# design_god.net
KiCad netlist of a schematic drawn in EAGLE
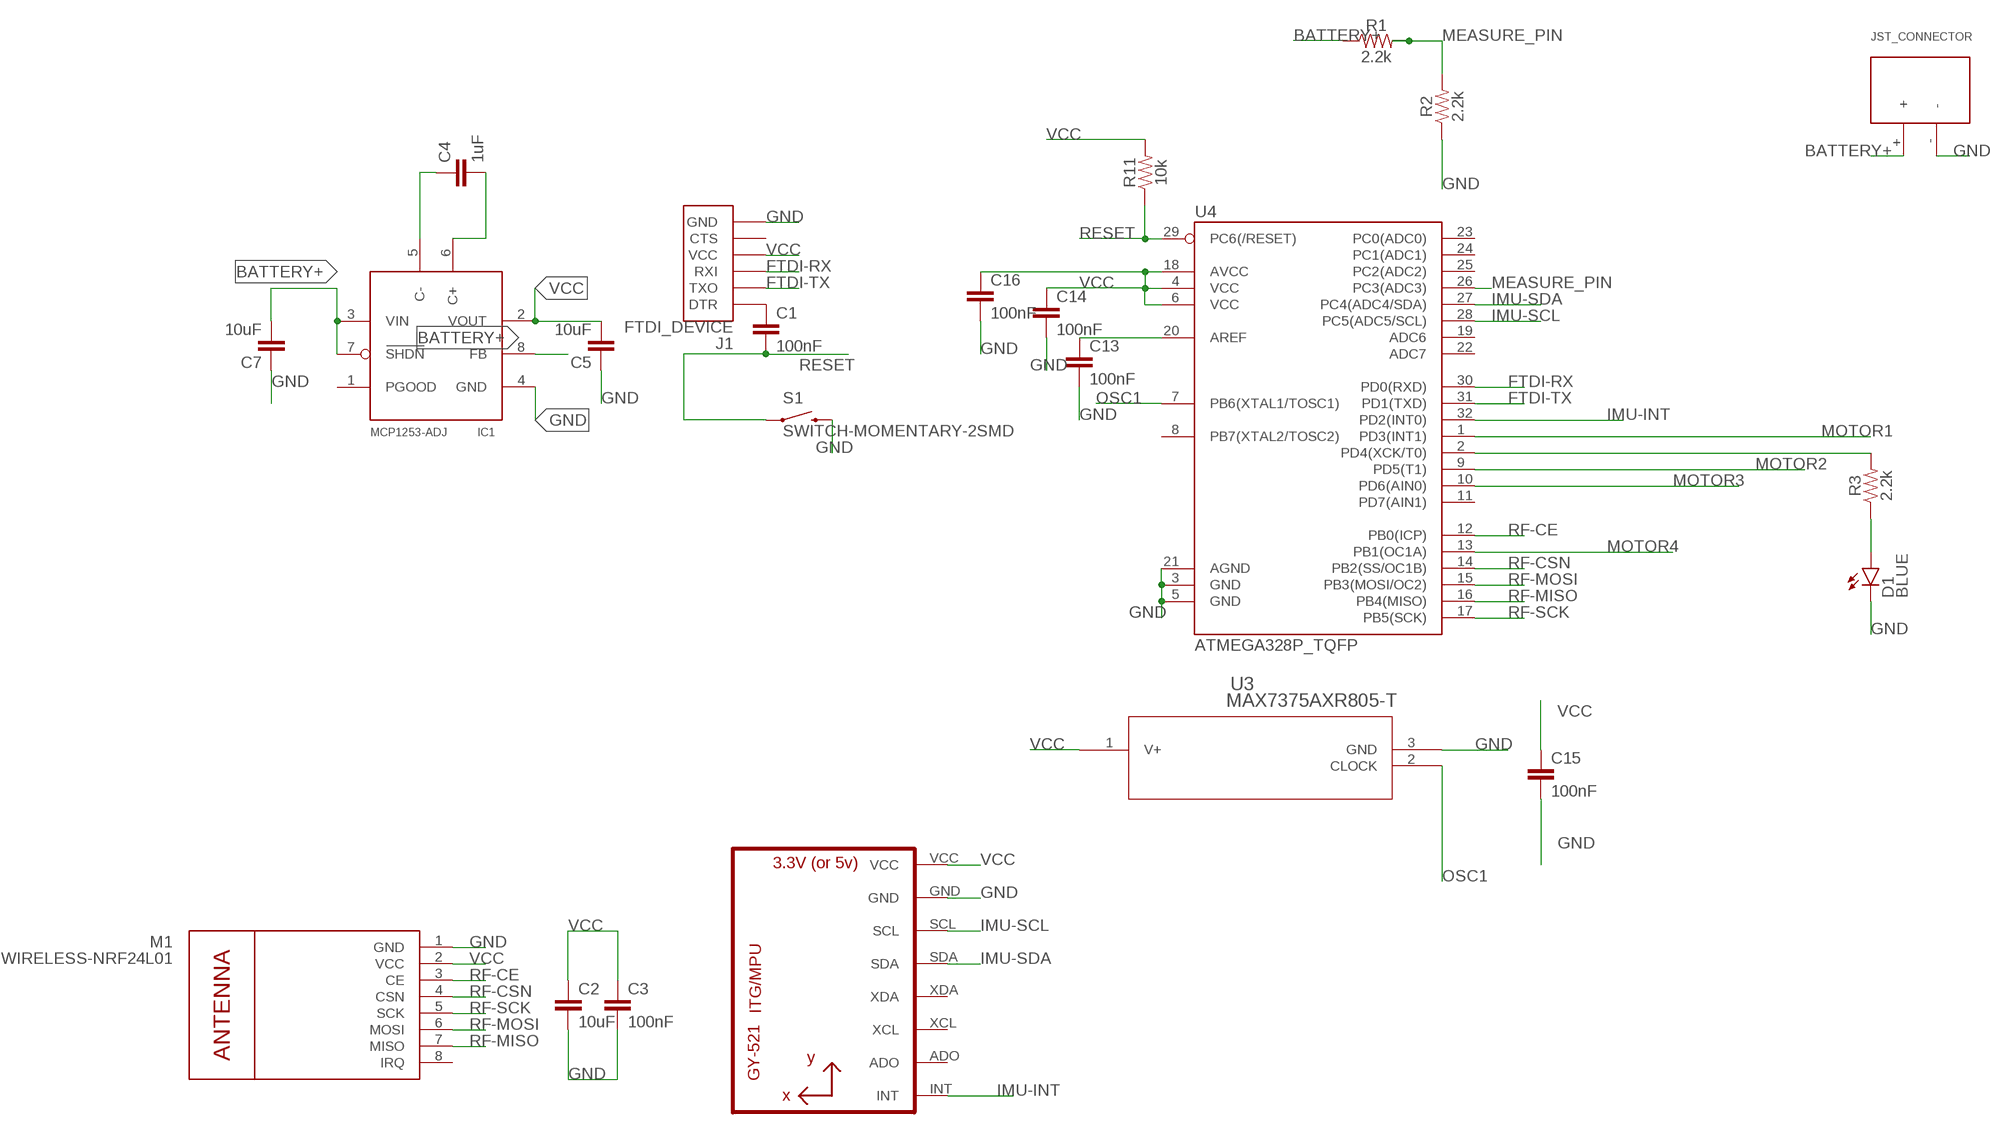
[diagram p0: schematic, sheet 1, part 1 of 2]
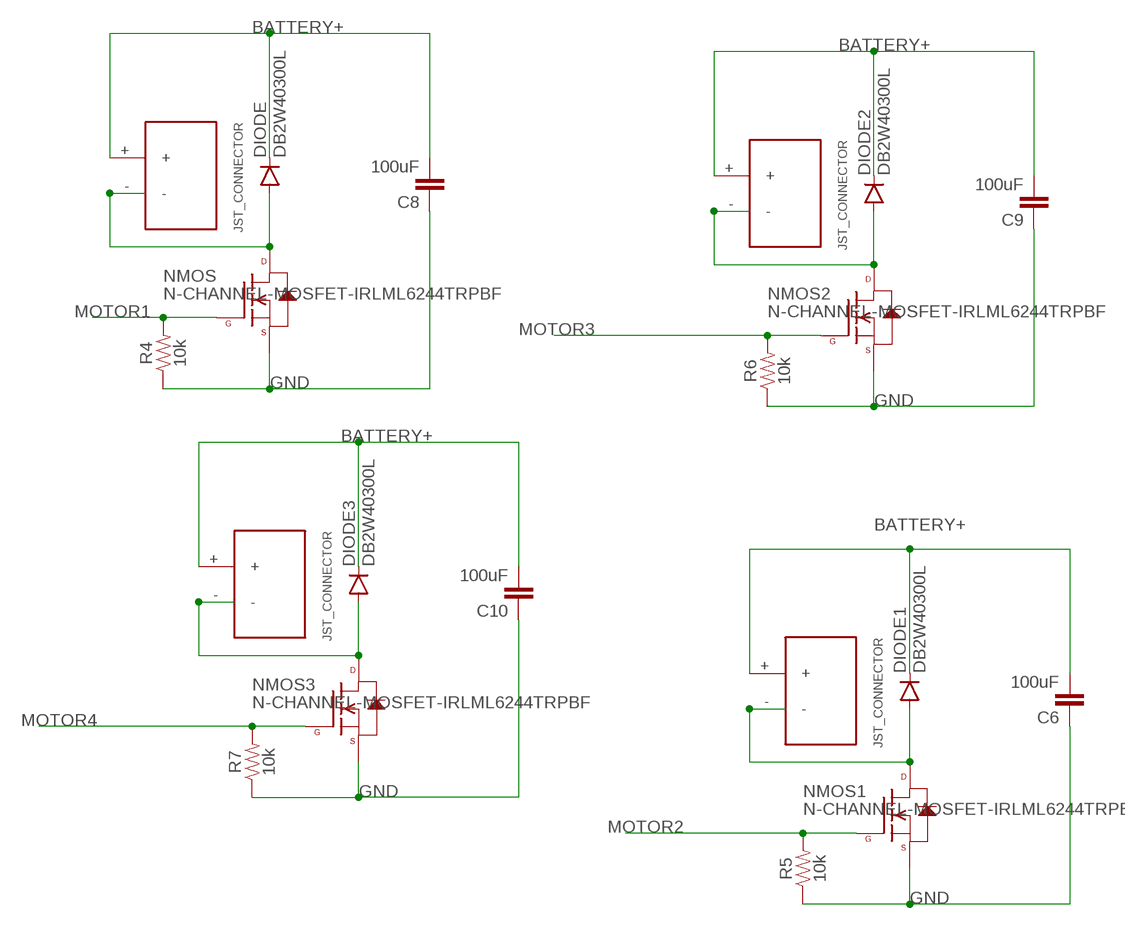
[diagram p1: schematic, sheet 1, part 2 of 2]

(export (version "E")
  (design (tool "Eeschema 10.0.6"))
  (components
    (comp (ref "C1")
      (value "100nF")
      (footprint "eagle-import:0603-CAP")
      (libsource (lib "eagle-import") (part "0.1UF-25V(+80/-20%)(0603)"))
    )
    (comp (ref "C2")
      (value "10uF")
      (footprint "eagle-import:0603-CAP")
      (libsource (lib "eagle-import") (part "CAP0603-CAP"))
    )
    (comp (ref "C3")
      (value "100nF")
      (footprint "eagle-import:0603-CAP")
      (libsource (lib "eagle-import") (part "CAP0603-CAP"))
    )
    (comp (ref "C4")
      (value "1uF")
      (footprint "eagle-import:0603-CAP")
      (libsource (lib "eagle-import") (part "0.1UF-25V(+80/-20%)(0603)"))
    )
    (comp (ref "C5")
      (value "10uF")
      (footprint "eagle-import:0603-CAP")
      (libsource (lib "eagle-import") (part "0.1UF-25V(+80/-20%)(0603)"))
    )
    (comp (ref "C6")
      (value "100uF")
      (footprint "eagle-import:1206")
      (libsource (lib "eagle-import") (part "CAP1206"))
    )
    (comp (ref "C7")
      (value "10uF")
      (footprint "eagle-import:0603-CAP")
      (libsource (lib "eagle-import") (part "0.1UF-25V(+80/-20%)(0603)"))
    )
    (comp (ref "C8")
      (value "100uF")
      (footprint "eagle-import:1206")
      (libsource (lib "eagle-import") (part "CAP1206"))
    )
    (comp (ref "C9")
      (value "100uF")
      (footprint "eagle-import:1206")
      (libsource (lib "eagle-import") (part "CAP1206"))
    )
    (comp (ref "C10")
      (value "100uF")
      (footprint "eagle-import:1206")
      (libsource (lib "eagle-import") (part "CAP1206"))
    )
    (comp (ref "C13")
      (value "100nF")
      (footprint "eagle-import:0603-CAP")
      (libsource (lib "eagle-import") (part "CAP0603-CAP"))
    )
    (comp (ref "C14")
      (value "100nF")
      (footprint "eagle-import:0603-CAP")
      (libsource (lib "eagle-import") (part "CAP0603-CAP"))
    )
    (comp (ref "C15")
      (value "100nF")
      (footprint "eagle-import:0603-CAP")
      (libsource (lib "eagle-import") (part "0.1UF-25V(+80/-20%)(0603)"))
    )
    (comp (ref "C16")
      (value "100nF")
      (footprint "eagle-import:0603-CAP")
      (libsource (lib "eagle-import") (part "CAP0603-CAP"))
    )
    (comp (ref "D1")
      (value "BLUE")
      (footprint "eagle-import:LED-0603")
      (fields (field (name "SPICEPREFIX") "D"))
      (libsource (lib "eagle-import") (part "LED-BLUE0603"))
    )
    (comp (ref "DIODE")
      (value "DB2W40300L")
      (footprint "eagle-import:MINI2-F3-B")
      (libsource (lib "eagle-import") (part "DB2W40300L"))
    )
    (comp (ref "DIODE1")
      (value "DB2W40300L")
      (footprint "eagle-import:MINI2-F3-B")
      (libsource (lib "eagle-import") (part "DB2W40300L"))
    )
    (comp (ref "DIODE2")
      (value "DB2W40300L")
      (footprint "eagle-import:MINI2-F3-B")
      (libsource (lib "eagle-import") (part "DB2W40300L"))
    )
    (comp (ref "DIODE3")
      (value "DB2W40300L")
      (footprint "eagle-import:MINI2-F3-B")
      (libsource (lib "eagle-import") (part "DB2W40300L"))
    )
    (comp (ref "IC1")
      (value "MCP1253-ADJ")
      (footprint "eagle-import:MSOP8")
      (libsource (lib "eagle-import") (part "MCP1253-ADJ"))
    )
    (comp (ref "J1")
      (value "FTDI_DEVICE")
      (footprint "eagle-import:FTDI_DEVICE_SIDE")
      (libsource (lib "eagle-import") (part "FTDI_DEVICE"))
    )
    (comp (ref "M1")
      (value "WIRELESS-NRF24L01")
      (footprint "eagle-import:WIRELESS-NRF24L01")
      (libsource (lib "eagle-import") (part "WIRELESS-NRF24L01"))
    )
    (comp (ref "MOTOR1")
      (value "JST_CONNECTOR_FEMALE")
      (footprint "eagle-import:JST_CONNECTOR_FEMALE")
      (libsource (lib "eagle-import") (part "JST_CONNECTOR_FEMALE"))
    )
    (comp (ref "MOTOR2")
      (value "JST_CONNECTOR_FEMALE")
      (footprint "eagle-import:JST_CONNECTOR_FEMALE")
      (libsource (lib "eagle-import") (part "JST_CONNECTOR_FEMALE"))
    )
    (comp (ref "MOTOR3")
      (value "JST_CONNECTOR_FEMALE")
      (footprint "eagle-import:JST_CONNECTOR_FEMALE")
      (libsource (lib "eagle-import") (part "JST_CONNECTOR_FEMALE"))
    )
    (comp (ref "MOTOR4")
      (value "JST_CONNECTOR_FEMALE")
      (footprint "eagle-import:JST_CONNECTOR_FEMALE")
      (libsource (lib "eagle-import") (part "JST_CONNECTOR_FEMALE"))
    )
    (comp (ref "NMOS")
      (value "N-CHANNEL-MOSFET-IRLML6244TRPBF")
      (footprint "eagle-import:SOT23-3")
      (libsource (lib "eagle-import") (part "N-CHANNEL-MOSFET-IRLML6244TRPBF"))
    )
    (comp (ref "NMOS1")
      (value "N-CHANNEL-MOSFET-IRLML6244TRPBF")
      (footprint "eagle-import:SOT23-3")
      (libsource (lib "eagle-import") (part "N-CHANNEL-MOSFET-IRLML6244TRPBF"))
    )
    (comp (ref "NMOS2")
      (value "N-CHANNEL-MOSFET-IRLML6244TRPBF")
      (footprint "eagle-import:SOT23-3")
      (libsource (lib "eagle-import") (part "N-CHANNEL-MOSFET-IRLML6244TRPBF"))
    )
    (comp (ref "NMOS3")
      (value "N-CHANNEL-MOSFET-IRLML6244TRPBF")
      (footprint "eagle-import:SOT23-3")
      (libsource (lib "eagle-import") (part "N-CHANNEL-MOSFET-IRLML6244TRPBF"))
    )
    (comp (ref "R1")
      (value "2.2k")
      (footprint "eagle-import:0603")
      (libsource (lib "eagle-import") (part "2.2KOHM-0603-1/10W-1%"))
    )
    (comp (ref "R2")
      (value "2.2k")
      (footprint "eagle-import:0603")
      (libsource (lib "eagle-import") (part "2.2KOHM-0603-1/10W-1%"))
    )
    (comp (ref "R3")
      (value "2.2k")
      (footprint "eagle-import:0603")
      (fields (field (name "SPICEPREFIX") "R"))
      (libsource (lib "eagle-import") (part "2.2KOHM-0603-1/10W-1%"))
    )
    (comp (ref "R4")
      (value "10k")
      (footprint "eagle-import:0603")
      (libsource (lib "eagle-import") (part "2.2KOHM-0603-1/10W-1%"))
    )
    (comp (ref "R5")
      (value "10k")
      (footprint "eagle-import:0603")
      (libsource (lib "eagle-import") (part "2.2KOHM-0603-1/10W-1%"))
    )
    (comp (ref "R6")
      (value "10k")
      (footprint "eagle-import:0603")
      (libsource (lib "eagle-import") (part "2.2KOHM-0603-1/10W-1%"))
    )
    (comp (ref "R7")
      (value "10k")
      (footprint "eagle-import:0603")
      (libsource (lib "eagle-import") (part "2.2KOHM-0603-1/10W-1%"))
    )
    (comp (ref "R11")
      (value "10k")
      (footprint "eagle-import:0603")
      (libsource (lib "eagle-import") (part "2.2KOHM-0603-1/10W-1%"))
    )
    (comp (ref "S1")
      (value "SWITCH-MOMENTARY-2SMD")
      (footprint "eagle-import:TACTILE-SWITCH-SMD")
      (libsource (lib "eagle-import") (part "SWITCH-MOMENTARY-2SMD"))
    )
    (comp (ref "U$1")
      (value "JST_CONNECTOR_FEMALE")
      (footprint "eagle-import:JST_CONNECTOR_FEMALE")
      (libsource (lib "eagle-import") (part "JST_CONNECTOR_FEMALE"))
    )
    (comp (ref "U2")
      (value "GY-521MPU6050")
      (footprint "eagle-import:GY-521")
      (libsource (lib "eagle-import") (part "GY-521MPU6050"))
    )
    (comp (ref "U3")
      (value "MAX7375AXR805-T")
      (footprint "eagle-import:21-0075D")
      (fields (field (name "MF") "Maxim Integrated") (field (name "MP") "MAX7375AXR805+T"))
      (libsource (lib "eagle-import") (part "MAX7375AXR805-T"))
    )
    (comp (ref "U4")
      (value "ATMEGA328P_TQFP")
      (footprint "eagle-import:TQFP32-08")
      (libsource (lib "eagle-import") (part "ATMEGA328P_TQFP"))
    )
  )
  (nets
    (net (code "1") (name "BATTERY+") (class "Default")
      (node (ref "C10") (pin "2") (pinfunction "2_2") (pintype "passive"))
      (node (ref "C6") (pin "2") (pinfunction "2_2") (pintype "passive"))
      (node (ref "C7") (pin "2") (pinfunction "2_2") (pintype "passive"))
      (node (ref "C8") (pin "2") (pinfunction "2_2") (pintype "passive"))
      (node (ref "C9") (pin "2") (pinfunction "2_2") (pintype "passive"))
      (node (ref "DIODE") (pin "NEG") (pinfunction "GPIN_NEG") (pintype "passive"))
      (node (ref "DIODE1") (pin "NEG") (pinfunction "GPIN_NEG") (pintype "passive"))
      (node (ref "DIODE2") (pin "NEG") (pinfunction "GPIN_NEG") (pintype "passive"))
      (node (ref "DIODE3") (pin "NEG") (pinfunction "GPIN_NEG") (pintype "passive"))
      (node (ref "IC1") (pin "3") (pinfunction "VIN_3") (pintype "power_in"))
      (node (ref "IC1") (pin "7") (pinfunction "SHDN_7") (pintype "input"))
      (node (ref "IC1") (pin "8") (pinfunction "FB_8") (pintype "input"))
      (node (ref "MOTOR1") (pin "+") (pinfunction "+_+") (pintype "bidirectional"))
      (node (ref "MOTOR2") (pin "+") (pinfunction "+_+") (pintype "bidirectional"))
      (node (ref "MOTOR3") (pin "+") (pinfunction "+_+") (pintype "bidirectional"))
      (node (ref "MOTOR4") (pin "+") (pinfunction "+_+") (pintype "bidirectional"))
      (node (ref "R1") (pin "1") (pinfunction "1_1") (pintype "passive"))
      (node (ref "U$1") (pin "+") (pinfunction "+_+") (pintype "bidirectional"))
    )
    (net (code "2") (name "FTDI-RX") (class "Default")
      (node (ref "J1") (pin "P$3") (pinfunction "RXI_P$3") (pintype "bidirectional"))
      (node (ref "U4") (pin "30") (pinfunction "PD0(RXD)_30") (pintype "bidirectional"))
    )
    (net (code "3") (name "FTDI-TX") (class "Default")
      (node (ref "J1") (pin "P$2") (pinfunction "TXO_P$2") (pintype "bidirectional"))
      (node (ref "U4") (pin "31") (pinfunction "PD1(TXD)_31") (pintype "bidirectional"))
    )
    (net (code "4") (name "GND") (class "Default")
      (node (ref "C10") (pin "1") (pinfunction "1_1") (pintype "passive"))
      (node (ref "C13") (pin "2") (pinfunction "2_2") (pintype "passive"))
      (node (ref "C14") (pin "2") (pinfunction "2_2") (pintype "passive"))
      (node (ref "C15") (pin "2") (pinfunction "2_2") (pintype "passive"))
      (node (ref "C16") (pin "2") (pinfunction "2_2") (pintype "passive"))
      (node (ref "C2") (pin "2") (pinfunction "2_2") (pintype "passive"))
      (node (ref "C3") (pin "2") (pinfunction "2_2") (pintype "passive"))
      (node (ref "C5") (pin "1") (pinfunction "1_1") (pintype "passive"))
      (node (ref "C6") (pin "1") (pinfunction "1_1") (pintype "passive"))
      (node (ref "C7") (pin "1") (pinfunction "1_1") (pintype "passive"))
      (node (ref "C8") (pin "1") (pinfunction "1_1") (pintype "passive"))
      (node (ref "C9") (pin "1") (pinfunction "1_1") (pintype "passive"))
      (node (ref "D1") (pin "C") (pinfunction "C_C") (pintype "passive"))
      (node (ref "IC1") (pin "4") (pinfunction "GND_4") (pintype "power_in"))
      (node (ref "J1") (pin "P$6") (pinfunction "GND_P$6") (pintype "bidirectional"))
      (node (ref "M1") (pin "1") (pinfunction "GND_1") (pintype "power_in"))
      (node (ref "NMOS") (pin "2") (pinfunction "S_2") (pintype "passive"))
      (node (ref "NMOS1") (pin "2") (pinfunction "S_2") (pintype "passive"))
      (node (ref "NMOS2") (pin "2") (pinfunction "S_2") (pintype "passive"))
      (node (ref "NMOS3") (pin "2") (pinfunction "S_2") (pintype "passive"))
      (node (ref "R2") (pin "1") (pinfunction "1_1") (pintype "passive"))
      (node (ref "R4") (pin "1") (pinfunction "1_1") (pintype "passive"))
      (node (ref "R5") (pin "1") (pinfunction "1_1") (pintype "passive"))
      (node (ref "R6") (pin "1") (pinfunction "1_1") (pintype "passive"))
      (node (ref "R7") (pin "1") (pinfunction "1_1") (pintype "passive"))
      (node (ref "S1") (pin "3") (pinfunction "2_3") (pintype "passive"))
      (node (ref "U$1") (pin "-") (pinfunction "-_-") (pintype "bidirectional"))
      (node (ref "U2") (pin "GND") (pinfunction "GND_GND") (pintype "bidirectional"))
      (node (ref "U3") (pin "3") (pinfunction "GND_3") (pintype "power_in"))
      (node (ref "U4") (pin "21") (pinfunction "AGND_21") (pintype "bidirectional"))
      (node (ref "U4") (pin "3") (pinfunction "GND_3") (pintype "bidirectional"))
      (node (ref "U4") (pin "5") (pinfunction "GND_5") (pintype "bidirectional"))
    )
    (net (code "5") (name "IMU-INT") (class "Default")
      (node (ref "U2") (pin "INT") (pinfunction "INT_INT") (pintype "bidirectional"))
      (node (ref "U4") (pin "32") (pinfunction "PD2(INT0)_32") (pintype "bidirectional"))
    )
    (net (code "6") (name "IMU-SCL") (class "Default")
      (node (ref "U2") (pin "SCL") (pinfunction "SCL_SCL") (pintype "bidirectional"))
      (node (ref "U4") (pin "28") (pinfunction "PC5(ADC5/SCL)_28") (pintype "bidirectional"))
    )
    (net (code "7") (name "IMU-SDA") (class "Default")
      (node (ref "U2") (pin "SDA") (pinfunction "SDA_SDA") (pintype "bidirectional"))
      (node (ref "U4") (pin "27") (pinfunction "PC4(ADC4/SDA)_27") (pintype "bidirectional"))
    )
    (net (code "8") (name "MEASURE_PIN") (class "Default")
      (node (ref "R1") (pin "2") (pinfunction "2_2") (pintype "passive"))
      (node (ref "R2") (pin "2") (pinfunction "2_2") (pintype "passive"))
      (node (ref "U4") (pin "26") (pinfunction "PC3(ADC3)_26") (pintype "bidirectional"))
    )
    (net (code "9") (name "MOTOR1") (class "Default")
      (node (ref "NMOS") (pin "1") (pinfunction "G_1") (pintype "passive"))
      (node (ref "R4") (pin "2") (pinfunction "2_2") (pintype "passive"))
      (node (ref "U4") (pin "1") (pinfunction "PD3(INT1)_1") (pintype "bidirectional"))
    )
    (net (code "10") (name "MOTOR2") (class "Default")
      (node (ref "NMOS1") (pin "1") (pinfunction "G_1") (pintype "passive"))
      (node (ref "R5") (pin "2") (pinfunction "2_2") (pintype "passive"))
      (node (ref "U4") (pin "9") (pinfunction "PD5(T1)_9") (pintype "bidirectional"))
    )
    (net (code "11") (name "MOTOR3") (class "Default")
      (node (ref "NMOS2") (pin "1") (pinfunction "G_1") (pintype "passive"))
      (node (ref "R6") (pin "2") (pinfunction "2_2") (pintype "passive"))
      (node (ref "U4") (pin "10") (pinfunction "PD6(AIN0)_10") (pintype "bidirectional"))
    )
    (net (code "12") (name "MOTOR4") (class "Default")
      (node (ref "NMOS3") (pin "1") (pinfunction "G_1") (pintype "passive"))
      (node (ref "R7") (pin "2") (pinfunction "2_2") (pintype "passive"))
      (node (ref "U4") (pin "13") (pinfunction "PB1(OC1A)_13") (pintype "bidirectional"))
    )
    (net (code "13") (name "Net-(D1-PadA)") (class "Default")
      (node (ref "D1") (pin "A") (pinfunction "A_A") (pintype "passive"))
      (node (ref "R3") (pin "1") (pinfunction "1_1") (pintype "passive"))
    )
    (net (code "14") (name "Net-(DIODE-PPIN)") (class "Default")
      (node (ref "DIODE") (pin "POS") (pinfunction "PPIN_POS") (pintype "passive"))
      (node (ref "MOTOR1") (pin "-") (pinfunction "-_-") (pintype "bidirectional"))
      (node (ref "NMOS") (pin "3") (pinfunction "D_3") (pintype "passive"))
    )
    (net (code "15") (name "Net-(DIODE1-PPIN)") (class "Default")
      (node (ref "DIODE1") (pin "POS") (pinfunction "PPIN_POS") (pintype "passive"))
      (node (ref "MOTOR2") (pin "-") (pinfunction "-_-") (pintype "bidirectional"))
      (node (ref "NMOS1") (pin "3") (pinfunction "D_3") (pintype "passive"))
    )
    (net (code "16") (name "Net-(DIODE2-PPIN)") (class "Default")
      (node (ref "DIODE2") (pin "POS") (pinfunction "PPIN_POS") (pintype "passive"))
      (node (ref "MOTOR3") (pin "-") (pinfunction "-_-") (pintype "bidirectional"))
      (node (ref "NMOS2") (pin "3") (pinfunction "D_3") (pintype "passive"))
    )
    (net (code "17") (name "Net-(DIODE3-PPIN)") (class "Default")
      (node (ref "DIODE3") (pin "POS") (pinfunction "PPIN_POS") (pintype "passive"))
      (node (ref "MOTOR4") (pin "-") (pinfunction "-_-") (pintype "bidirectional"))
      (node (ref "NMOS3") (pin "3") (pinfunction "D_3") (pintype "passive"))
    )
    (net (code "18") (name "Net-(IC1-C+)") (class "Default")
      (node (ref "C4") (pin "2") (pinfunction "2_2") (pintype "passive"))
      (node (ref "IC1") (pin "6") (pinfunction "C+_6") (pintype "passive"))
    )
    (net (code "19") (name "Net-(IC1-C-)") (class "Default")
      (node (ref "C4") (pin "1") (pinfunction "1_1") (pintype "passive"))
      (node (ref "IC1") (pin "5") (pinfunction "C-_5") (pintype "passive"))
    )
    (net (code "20") (name "Net-(J1-DTR)") (class "Default")
      (node (ref "C1") (pin "1") (pinfunction "1_1") (pintype "passive"))
      (node (ref "J1") (pin "P$1") (pinfunction "DTR_P$1") (pintype "bidirectional"))
    )
    (net (code "21") (name "Net-(U4-AREF)") (class "Default")
      (node (ref "C13") (pin "1") (pinfunction "1_1") (pintype "passive"))
      (node (ref "U4") (pin "20") (pinfunction "AREF_20") (pintype "bidirectional"))
    )
    (net (code "22") (name "Net-(U4-PD4(XCK{slash}T0))") (class "Default")
      (node (ref "R3") (pin "2") (pinfunction "2_2") (pintype "passive"))
      (node (ref "U4") (pin "2") (pinfunction "PD4(XCK/T0)_2") (pintype "bidirectional"))
    )
    (net (code "23") (name "OSC1") (class "Default")
      (node (ref "U3") (pin "2") (pinfunction "CLOCK_2") (pintype "output"))
      (node (ref "U4") (pin "7") (pinfunction "PB6(XTAL1/TOSC1)_7") (pintype "bidirectional"))
    )
    (net (code "24") (name "RESET") (class "Default")
      (node (ref "C1") (pin "2") (pinfunction "2_2") (pintype "passive"))
      (node (ref "R11") (pin "1") (pinfunction "1_1") (pintype "passive"))
      (node (ref "S1") (pin "1") (pinfunction "1_1") (pintype "passive"))
      (node (ref "U4") (pin "29") (pinfunction "PC6(/RESET)_29") (pintype "bidirectional"))
    )
    (net (code "25") (name "RF-CE") (class "Default")
      (node (ref "M1") (pin "3") (pinfunction "CE_3") (pintype "bidirectional"))
      (node (ref "U4") (pin "12") (pinfunction "PB0(ICP)_12") (pintype "bidirectional"))
    )
    (net (code "26") (name "RF-CSN") (class "Default")
      (node (ref "M1") (pin "4") (pinfunction "CSN_4") (pintype "bidirectional"))
      (node (ref "U4") (pin "14") (pinfunction "PB2(SS/OC1B)_14") (pintype "bidirectional"))
    )
    (net (code "27") (name "RF-MISO") (class "Default")
      (node (ref "M1") (pin "7") (pinfunction "MISO_7") (pintype "bidirectional"))
      (node (ref "U4") (pin "16") (pinfunction "PB4(MISO)_16") (pintype "bidirectional"))
    )
    (net (code "28") (name "RF-MOSI") (class "Default")
      (node (ref "M1") (pin "6") (pinfunction "MOSI_6") (pintype "bidirectional"))
      (node (ref "U4") (pin "15") (pinfunction "PB3(MOSI/OC2)_15") (pintype "bidirectional"))
    )
    (net (code "29") (name "RF-SCK") (class "Default")
      (node (ref "M1") (pin "5") (pinfunction "SCK_5") (pintype "bidirectional"))
      (node (ref "U4") (pin "17") (pinfunction "PB5(SCK)_17") (pintype "bidirectional"))
    )
    (net (code "30") (name "VCC") (class "Default")
      (node (ref "C14") (pin "1") (pinfunction "1_1") (pintype "passive"))
      (node (ref "C15") (pin "1") (pinfunction "1_1") (pintype "passive"))
      (node (ref "C16") (pin "1") (pinfunction "1_1") (pintype "passive"))
      (node (ref "C2") (pin "1") (pinfunction "1_1") (pintype "passive"))
      (node (ref "C3") (pin "1") (pinfunction "1_1") (pintype "passive"))
      (node (ref "C5") (pin "2") (pinfunction "2_2") (pintype "passive"))
      (node (ref "IC1") (pin "2") (pinfunction "VOUT_2") (pintype "output"))
      (node (ref "J1") (pin "P$4") (pinfunction "VCC_P$4") (pintype "bidirectional"))
      (node (ref "M1") (pin "2") (pinfunction "VCC_2") (pintype "power_in"))
      (node (ref "R11") (pin "2") (pinfunction "2_2") (pintype "passive"))
      (node (ref "U2") (pin "VCC") (pinfunction "VCC_VCC") (pintype "bidirectional"))
      (node (ref "U3") (pin "1") (pinfunction "V+_1") (pintype "power_in"))
      (node (ref "U4") (pin "18") (pinfunction "AVCC_18") (pintype "bidirectional"))
      (node (ref "U4") (pin "4") (pinfunction "VCC_4") (pintype "bidirectional"))
      (node (ref "U4") (pin "6") (pinfunction "VCC_6") (pintype "bidirectional"))
    )
    (net (code "31") (name "unconnected-(IC1-PGOOD-Pad1)") (class "Default")
      (node (ref "IC1") (pin "1") (pinfunction "PGOOD_1") (pintype "output"))
    )
    (net (code "32") (name "unconnected-(J1-CTS-PadP$5)") (class "Default")
      (node (ref "J1") (pin "P$5") (pinfunction "CTS_P$5") (pintype "bidirectional"))
    )
    (net (code "33") (name "unconnected-(M1-IRQ-Pad8)") (class "Default")
      (node (ref "M1") (pin "8") (pinfunction "IRQ_8") (pintype "bidirectional"))
    )
    (net (code "34") (name "unconnected-(U2-PadADO)") (class "Default")
      (node (ref "U2") (pin "ADO") (pinfunction "ADO_ADO") (pintype "bidirectional"))
    )
    (net (code "35") (name "unconnected-(U2-PadXCL)") (class "Default")
      (node (ref "U2") (pin "XCL") (pinfunction "XCL_XCL") (pintype "bidirectional"))
    )
    (net (code "36") (name "unconnected-(U2-PadXDA)") (class "Default")
      (node (ref "U2") (pin "XDA") (pinfunction "XDA_XDA") (pintype "bidirectional"))
    )
    (net (code "37") (name "unconnected-(U4-ADC6-Pad19)") (class "Default")
      (node (ref "U4") (pin "19") (pinfunction "ADC6_19") (pintype "bidirectional"))
    )
    (net (code "38") (name "unconnected-(U4-ADC7-Pad22)") (class "Default")
      (node (ref "U4") (pin "22") (pinfunction "ADC7_22") (pintype "bidirectional"))
    )
    (net (code "39") (name "unconnected-(U4-PB7(XTAL2{slash}TOSC2)-Pad8)") (class "Default")
      (node (ref "U4") (pin "8") (pinfunction "PB7(XTAL2/TOSC2)_8") (pintype "bidirectional"))
    )
    (net (code "40") (name "unconnected-(U4-PC0(ADC0)-Pad23)") (class "Default")
      (node (ref "U4") (pin "23") (pinfunction "PC0(ADC0)_23") (pintype "bidirectional"))
    )
    (net (code "41") (name "unconnected-(U4-PC1(ADC1)-Pad24)") (class "Default")
      (node (ref "U4") (pin "24") (pinfunction "PC1(ADC1)_24") (pintype "bidirectional"))
    )
    (net (code "42") (name "unconnected-(U4-PC2(ADC2)-Pad25)") (class "Default")
      (node (ref "U4") (pin "25") (pinfunction "PC2(ADC2)_25") (pintype "bidirectional"))
    )
    (net (code "43") (name "unconnected-(U4-PD7(AIN1)-Pad11)") (class "Default")
      (node (ref "U4") (pin "11") (pinfunction "PD7(AIN1)_11") (pintype "bidirectional"))
    )
  )
)
